# Top.net
KiCad netlist of a schematic drawn in Altium Designer
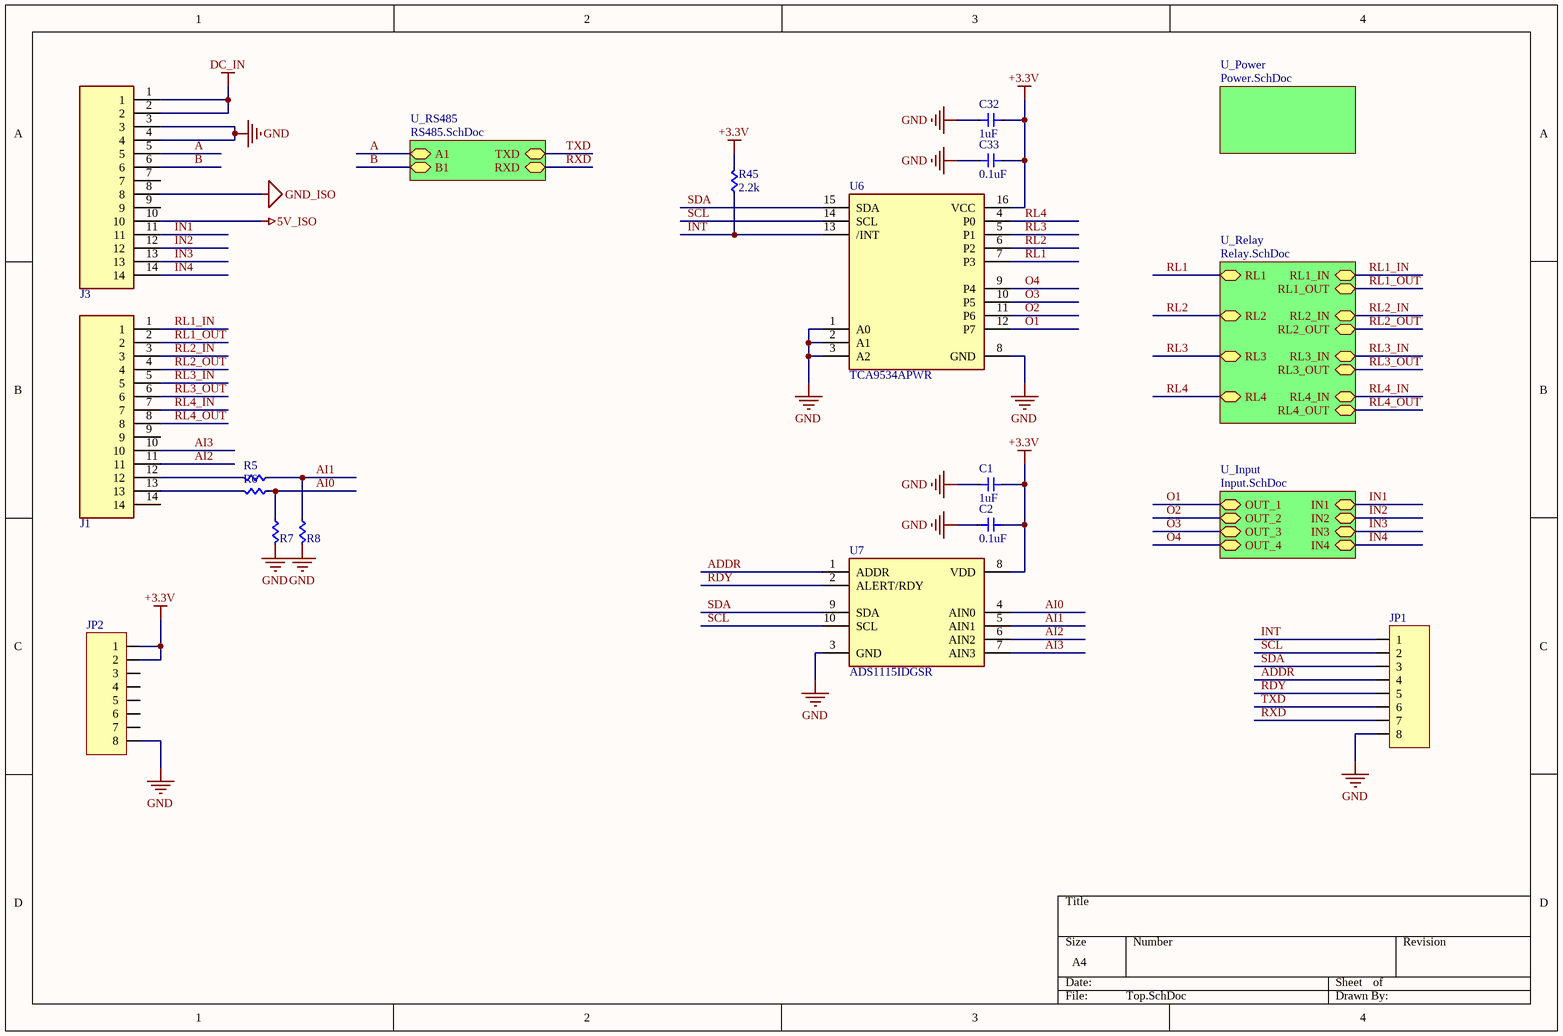
[diagram p0: Top.SchDoc]

(export (version "E")
  (design (tool "Eeschema 10.0.6"))
  (components
    (comp (ref "C1")
      (value "1uF")
      (footprint "Cap 0603")
      (description "Capacitor SMD 0603")
      (libsource (lib "Altium_Lib_PTK") (part "Cap 0603"))
    )
    (comp (ref "C2")
      (value "0.1uF")
      (footprint "Cap 0603")
      (description "Capacitor SMD 0603")
      (libsource (lib "Altium_Lib_PTK") (part "Cap 0603"))
    )
    (comp (ref "C32")
      (value "1uF")
      (footprint "Cap 0603")
      (description "Capacitor SMD 0603")
      (libsource (lib "Altium_Lib_PTK") (part "Cap 0603"))
    )
    (comp (ref "C33")
      (value "0.1uF")
      (footprint "Cap 0603")
      (description "Capacitor SMD 0603")
      (libsource (lib "Altium_Lib_PTK") (part "Cap 0603"))
    )
    (comp (ref "J1")
      (value "CON 14 EDGR 3.81 RA")
      (footprint "CON 14 EDGR 3.81 RA")
      (description "Pluggable,Receptacle, Horizontal, 3.81 Pitch, Terminal Block Connector")
      (fields
        (field (name "MF") "{'manufacturer': u'Same Sky (Formerly CUI Devices)'}")
        (field (name "MP") "TBP02R1-381-14BE")
      )
      (libsource (lib "Altium_Lib_PTK") (part "CON 14 EDGR 3.81 RA"))
    )
    (comp (ref "J3")
      (value "CON 14 EDGR 3.81 RA")
      (footprint "CON 14 EDGR 3.81 RA")
      (description "Pluggable,Receptacle, Horizontal, 3.81 Pitch, Terminal Block Connector")
      (fields
        (field (name "MF") "{'manufacturer': u'Same Sky (Formerly CUI Devices)'}")
        (field (name "MP") "TBP02R1-381-14BE")
      )
      (libsource (lib "Altium_Lib_PTK") (part "CON 14 EDGR 3.81 RA"))
    )
    (comp (ref "JP1")
      (value "JP 1x8 2.54")
      (footprint "JP 1x8 DT")
      (description "Cắm")
      (libsource (lib "") (part "JP 1x8 2.54 Duc Thang_1"))
    )
    (comp (ref "JP2")
      (value "JP 1x8 2.54")
      (footprint "JP 1x8 DT")
      (description "Cắm")
      (libsource (lib "Altium_Lib_PTK") (part "JP 1x8 2.54 Duc Thang"))
    )
    (comp (ref "R5")
      (value "RS1")
      (footprint "RES 0603")
      (description "RES SMD 0603")
      (fields
        (field (name "MANUFACTURER") "Vishay Dale")
        (field (name "MANUFACTURER PART NUMBER") "CRCW040210K0FKED")
      )
      (libsource (lib "Altium_Lib_PTK") (part "RES 0603"))
    )
    (comp (ref "R6")
      (value "RS1")
      (footprint "RES 0603")
      (description "RES SMD 0603")
      (fields
        (field (name "MANUFACTURER") "Vishay Dale")
        (field (name "MANUFACTURER PART NUMBER") "CRCW040210K0FKED")
      )
      (libsource (lib "Altium_Lib_PTK") (part "RES 0603"))
    )
    (comp (ref "R7")
      (value "RS2")
      (footprint "RES 0603")
      (description "RES SMD 0603")
      (fields
        (field (name "MANUFACTURER") "Vishay Dale")
        (field (name "MANUFACTURER PART NUMBER") "CRCW040210K0FKED")
      )
      (libsource (lib "Altium_Lib_PTK") (part "RES 0603"))
    )
    (comp (ref "R8")
      (value "RS2")
      (footprint "RES 0603")
      (description "RES SMD 0603")
      (fields
        (field (name "MANUFACTURER") "Vishay Dale")
        (field (name "MANUFACTURER PART NUMBER") "CRCW040210K0FKED")
      )
      (libsource (lib "Altium_Lib_PTK") (part "RES 0603"))
    )
    (comp (ref "R45")
      (value "2.2k")
      (footprint "RES 0603")
      (description "RES SMD 0603")
      (fields
        (field (name "MANUFACTURER") "Vishay Dale")
        (field (name "MANUFACTURER PART NUMBER") "CRCW040210K0FKED")
      )
      (libsource (lib "Altium_Lib_PTK") (part "RES 0603"))
    )
    (comp (ref "U6")
      (value "TCA9534APWR")
      (footprint "SOP65P640X120-16N")
      (description "8-bit 1.65- to 5.5-V I2C/SMBus I/O expander with interrupt, & config registers")
      (fields (field (name "MF") "Texas Instruments"))
      (libsource (lib "Altium_Lib_PTK") (part "TCA9534APWR"))
    )
    (comp (ref "U7")
      (value "ADS1115IDGSR")
      (footprint "SOP50P490X110-10N")
      (description "16-bit, 860-SPS, 4-channel, delta-sigma ADC with PGA, oscillator, VREF, comparator and I2C")
      (fields (field (name "MF") "Texas Instruments"))
      (libsource (lib "Altium_Lib_PTK") (part "ADS1115IDGSR"))
    )
  )
  (nets
    (net (code "1") (name "+3.3V") (class "Default")
      (node (ref "C1") (pin "1") (pinfunction "1_1") (pintype "passive"))
      (node (ref "C2") (pin "1") (pinfunction "1_1") (pintype "passive"))
      (node (ref "C32") (pin "1") (pinfunction "1_1") (pintype "passive"))
      (node (ref "C33") (pin "1") (pinfunction "1_1") (pintype "passive"))
      (node (ref "JP2") (pin "1") (pinfunction "1_1") (pintype "passive"))
      (node (ref "JP2") (pin "2") (pinfunction "2_2") (pintype "passive"))
      (node (ref "R45") (pin "2") (pinfunction "2_2") (pintype "passive"))
      (node (ref "U6") (pin "16") (pinfunction "VCC_16") (pintype "power_in"))
      (node (ref "U7") (pin "8") (pinfunction "VDD_8") (pintype "power_in"))
    )
    (net (code "2") (name "/A") (class "Default")
      (node (ref "J3") (pin "5") (pinfunction "5_5") (pintype "passive"))
    )
    (net (code "3") (name "/ADDR") (class "Default")
      (node (ref "JP1") (pin "4") (pinfunction "4_4") (pintype "passive"))
      (node (ref "U7") (pin "1") (pinfunction "ADDR_1") (pintype "passive"))
    )
    (net (code "4") (name "/AI0") (class "Default")
      (node (ref "R6") (pin "1") (pinfunction "1_1") (pintype "passive"))
      (node (ref "R7") (pin "1") (pinfunction "1_1") (pintype "passive"))
      (node (ref "U7") (pin "4") (pinfunction "AIN0_4") (pintype "passive"))
    )
    (net (code "5") (name "/AI1") (class "Default")
      (node (ref "R5") (pin "1") (pinfunction "1_1") (pintype "passive"))
      (node (ref "R8") (pin "1") (pinfunction "1_1") (pintype "passive"))
      (node (ref "U7") (pin "5") (pinfunction "AIN1_5") (pintype "passive"))
    )
    (net (code "6") (name "/AI2") (class "Default")
      (node (ref "J1") (pin "11") (pinfunction "11_11") (pintype "passive"))
      (node (ref "U7") (pin "6") (pinfunction "AIN2_6") (pintype "passive"))
    )
    (net (code "7") (name "/AI3") (class "Default")
      (node (ref "J1") (pin "10") (pinfunction "10_10") (pintype "passive"))
      (node (ref "U7") (pin "7") (pinfunction "AIN3_7") (pintype "passive"))
    )
    (net (code "8") (name "/B") (class "Default")
      (node (ref "J3") (pin "6") (pinfunction "6_6") (pintype "passive"))
    )
    (net (code "9") (name "/IN1") (class "Default")
      (node (ref "J3") (pin "11") (pinfunction "11_11") (pintype "passive"))
    )
    (net (code "10") (name "/IN2") (class "Default")
      (node (ref "J3") (pin "12") (pinfunction "12_12") (pintype "passive"))
    )
    (net (code "11") (name "/IN3") (class "Default")
      (node (ref "J3") (pin "13") (pinfunction "13_13") (pintype "passive"))
    )
    (net (code "12") (name "/IN4") (class "Default")
      (node (ref "J3") (pin "14") (pinfunction "14_14") (pintype "passive"))
    )
    (net (code "13") (name "/INT") (class "Default")
      (node (ref "JP1") (pin "1") (pinfunction "1_1") (pintype "passive"))
      (node (ref "R45") (pin "1") (pinfunction "1_1") (pintype "passive"))
      (node (ref "U6") (pin "13") (pinfunction "/INT_13") (pintype "passive"))
    )
    (net (code "14") (name "/O1") (class "Default")
      (node (ref "U6") (pin "12") (pinfunction "P7_12") (pintype "passive"))
    )
    (net (code "15") (name "/O2") (class "Default")
      (node (ref "U6") (pin "11") (pinfunction "P6_11") (pintype "passive"))
    )
    (net (code "16") (name "/O3") (class "Default")
      (node (ref "U6") (pin "10") (pinfunction "P5_10") (pintype "passive"))
    )
    (net (code "17") (name "/O4") (class "Default")
      (node (ref "U6") (pin "9") (pinfunction "P4_9") (pintype "passive"))
    )
    (net (code "18") (name "/RDY") (class "Default")
      (node (ref "JP1") (pin "5") (pinfunction "5_5") (pintype "passive"))
      (node (ref "U7") (pin "2") (pinfunction "ALERT/RDY_2") (pintype "passive"))
    )
    (net (code "19") (name "/RL1") (class "Default")
      (node (ref "U6") (pin "7") (pinfunction "P3_7") (pintype "passive"))
    )
    (net (code "20") (name "/RL1_IN") (class "Default")
      (node (ref "J1") (pin "1") (pinfunction "1_1") (pintype "passive"))
    )
    (net (code "21") (name "/RL1_OUT") (class "Default")
      (node (ref "J1") (pin "2") (pinfunction "2_2") (pintype "passive"))
    )
    (net (code "22") (name "/RL2") (class "Default")
      (node (ref "U6") (pin "6") (pinfunction "P2_6") (pintype "passive"))
    )
    (net (code "23") (name "/RL2_IN") (class "Default")
      (node (ref "J1") (pin "3") (pinfunction "3_3") (pintype "passive"))
    )
    (net (code "24") (name "/RL2_OUT") (class "Default")
      (node (ref "J1") (pin "4") (pinfunction "4_4") (pintype "passive"))
    )
    (net (code "25") (name "/RL3") (class "Default")
      (node (ref "U6") (pin "5") (pinfunction "P1_5") (pintype "passive"))
    )
    (net (code "26") (name "/RL3_IN") (class "Default")
      (node (ref "J1") (pin "5") (pinfunction "5_5") (pintype "passive"))
    )
    (net (code "27") (name "/RL3_OUT") (class "Default")
      (node (ref "J1") (pin "6") (pinfunction "6_6") (pintype "passive"))
    )
    (net (code "28") (name "/RL4") (class "Default")
      (node (ref "U6") (pin "4") (pinfunction "P0_4") (pintype "passive"))
    )
    (net (code "29") (name "/RL4_IN") (class "Default")
      (node (ref "J1") (pin "7") (pinfunction "7_7") (pintype "passive"))
    )
    (net (code "30") (name "/RL4_OUT") (class "Default")
      (node (ref "J1") (pin "8") (pinfunction "8_8") (pintype "passive"))
    )
    (net (code "31") (name "/RXD") (class "Default")
      (node (ref "JP1") (pin "7") (pinfunction "7_7") (pintype "passive"))
    )
    (net (code "32") (name "/SCL") (class "Default")
      (node (ref "JP1") (pin "2") (pinfunction "2_2") (pintype "passive"))
      (node (ref "U6") (pin "14") (pinfunction "SCL_14") (pintype "passive"))
      (node (ref "U7") (pin "10") (pinfunction "SCL_10") (pintype "passive"))
    )
    (net (code "33") (name "/SDA") (class "Default")
      (node (ref "JP1") (pin "3") (pinfunction "3_3") (pintype "passive"))
      (node (ref "U6") (pin "15") (pinfunction "SDA_15") (pintype "passive"))
      (node (ref "U7") (pin "9") (pinfunction "SDA_9") (pintype "passive"))
    )
    (net (code "34") (name "/TXD") (class "Default")
      (node (ref "JP1") (pin "6") (pinfunction "6_6") (pintype "passive"))
    )
    (net (code "35") (name "5V_ISO") (class "Default")
      (node (ref "J3") (pin "10") (pinfunction "10_10") (pintype "passive"))
    )
    (net (code "36") (name "DC_IN") (class "Default")
      (node (ref "J3") (pin "1") (pinfunction "1_1") (pintype "passive"))
      (node (ref "J3") (pin "2") (pinfunction "2_2") (pintype "passive"))
    )
    (net (code "37") (name "GND") (class "Default")
      (node (ref "C1") (pin "2") (pinfunction "2_2") (pintype "passive"))
      (node (ref "C2") (pin "2") (pinfunction "2_2") (pintype "passive"))
      (node (ref "C32") (pin "2") (pinfunction "2_2") (pintype "passive"))
      (node (ref "C33") (pin "2") (pinfunction "2_2") (pintype "passive"))
      (node (ref "J3") (pin "3") (pinfunction "3_3") (pintype "passive"))
      (node (ref "J3") (pin "4") (pinfunction "4_4") (pintype "passive"))
      (node (ref "JP1") (pin "8") (pinfunction "8_8") (pintype "passive"))
      (node (ref "JP2") (pin "8") (pinfunction "8_8") (pintype "passive"))
      (node (ref "R7") (pin "2") (pinfunction "2_2") (pintype "passive"))
      (node (ref "R8") (pin "2") (pinfunction "2_2") (pintype "passive"))
      (node (ref "U6") (pin "1") (pinfunction "A0_1") (pintype "passive"))
      (node (ref "U6") (pin "2") (pinfunction "A1_2") (pintype "passive"))
      (node (ref "U6") (pin "3") (pinfunction "A2_3") (pintype "passive"))
      (node (ref "U6") (pin "8") (pinfunction "GND_8") (pintype "power_in"))
      (node (ref "U7") (pin "3") (pinfunction "GND_3") (pintype "power_in"))
    )
    (net (code "38") (name "GND_ISO") (class "Default")
      (node (ref "J3") (pin "8") (pinfunction "8_8") (pintype "passive"))
    )
    (net (code "39") (name "Net-(J1-Pad12)") (class "Default")
      (node (ref "J1") (pin "12") (pinfunction "12_12") (pintype "passive"))
      (node (ref "R5") (pin "2") (pinfunction "2_2") (pintype "passive"))
    )
    (net (code "40") (name "Net-(J1-Pad13)") (class "Default")
      (node (ref "J1") (pin "13") (pinfunction "13_13") (pintype "passive"))
      (node (ref "R6") (pin "2") (pinfunction "2_2") (pintype "passive"))
    )
    (net (code "41") (name "unconnected-(J1-Pad9)") (class "Default")
      (node (ref "J1") (pin "9") (pinfunction "9_9") (pintype "passive"))
    )
    (net (code "42") (name "unconnected-(J1-Pad14)") (class "Default")
      (node (ref "J1") (pin "14") (pinfunction "14_14") (pintype "passive"))
    )
    (net (code "43") (name "unconnected-(J3-Pad7)") (class "Default")
      (node (ref "J3") (pin "7") (pinfunction "7_7") (pintype "passive"))
    )
    (net (code "44") (name "unconnected-(J3-Pad9)") (class "Default")
      (node (ref "J3") (pin "9") (pinfunction "9_9") (pintype "passive"))
    )
    (net (code "45") (name "unconnected-(JP2-Pad3)") (class "Default")
      (node (ref "JP2") (pin "3") (pinfunction "3_3") (pintype "passive"))
    )
    (net (code "46") (name "unconnected-(JP2-Pad4)") (class "Default")
      (node (ref "JP2") (pin "4") (pinfunction "4_4") (pintype "passive"))
    )
    (net (code "47") (name "unconnected-(JP2-Pad5)") (class "Default")
      (node (ref "JP2") (pin "5") (pinfunction "5_5") (pintype "passive"))
    )
    (net (code "48") (name "unconnected-(JP2-Pad6)") (class "Default")
      (node (ref "JP2") (pin "6") (pinfunction "6_6") (pintype "passive"))
    )
    (net (code "49") (name "unconnected-(JP2-Pad7)") (class "Default")
      (node (ref "JP2") (pin "7") (pinfunction "7_7") (pintype "passive"))
    )
  )
)
